# photon_proto_shield.net
KiCad netlist of a schematic drawn in EAGLE
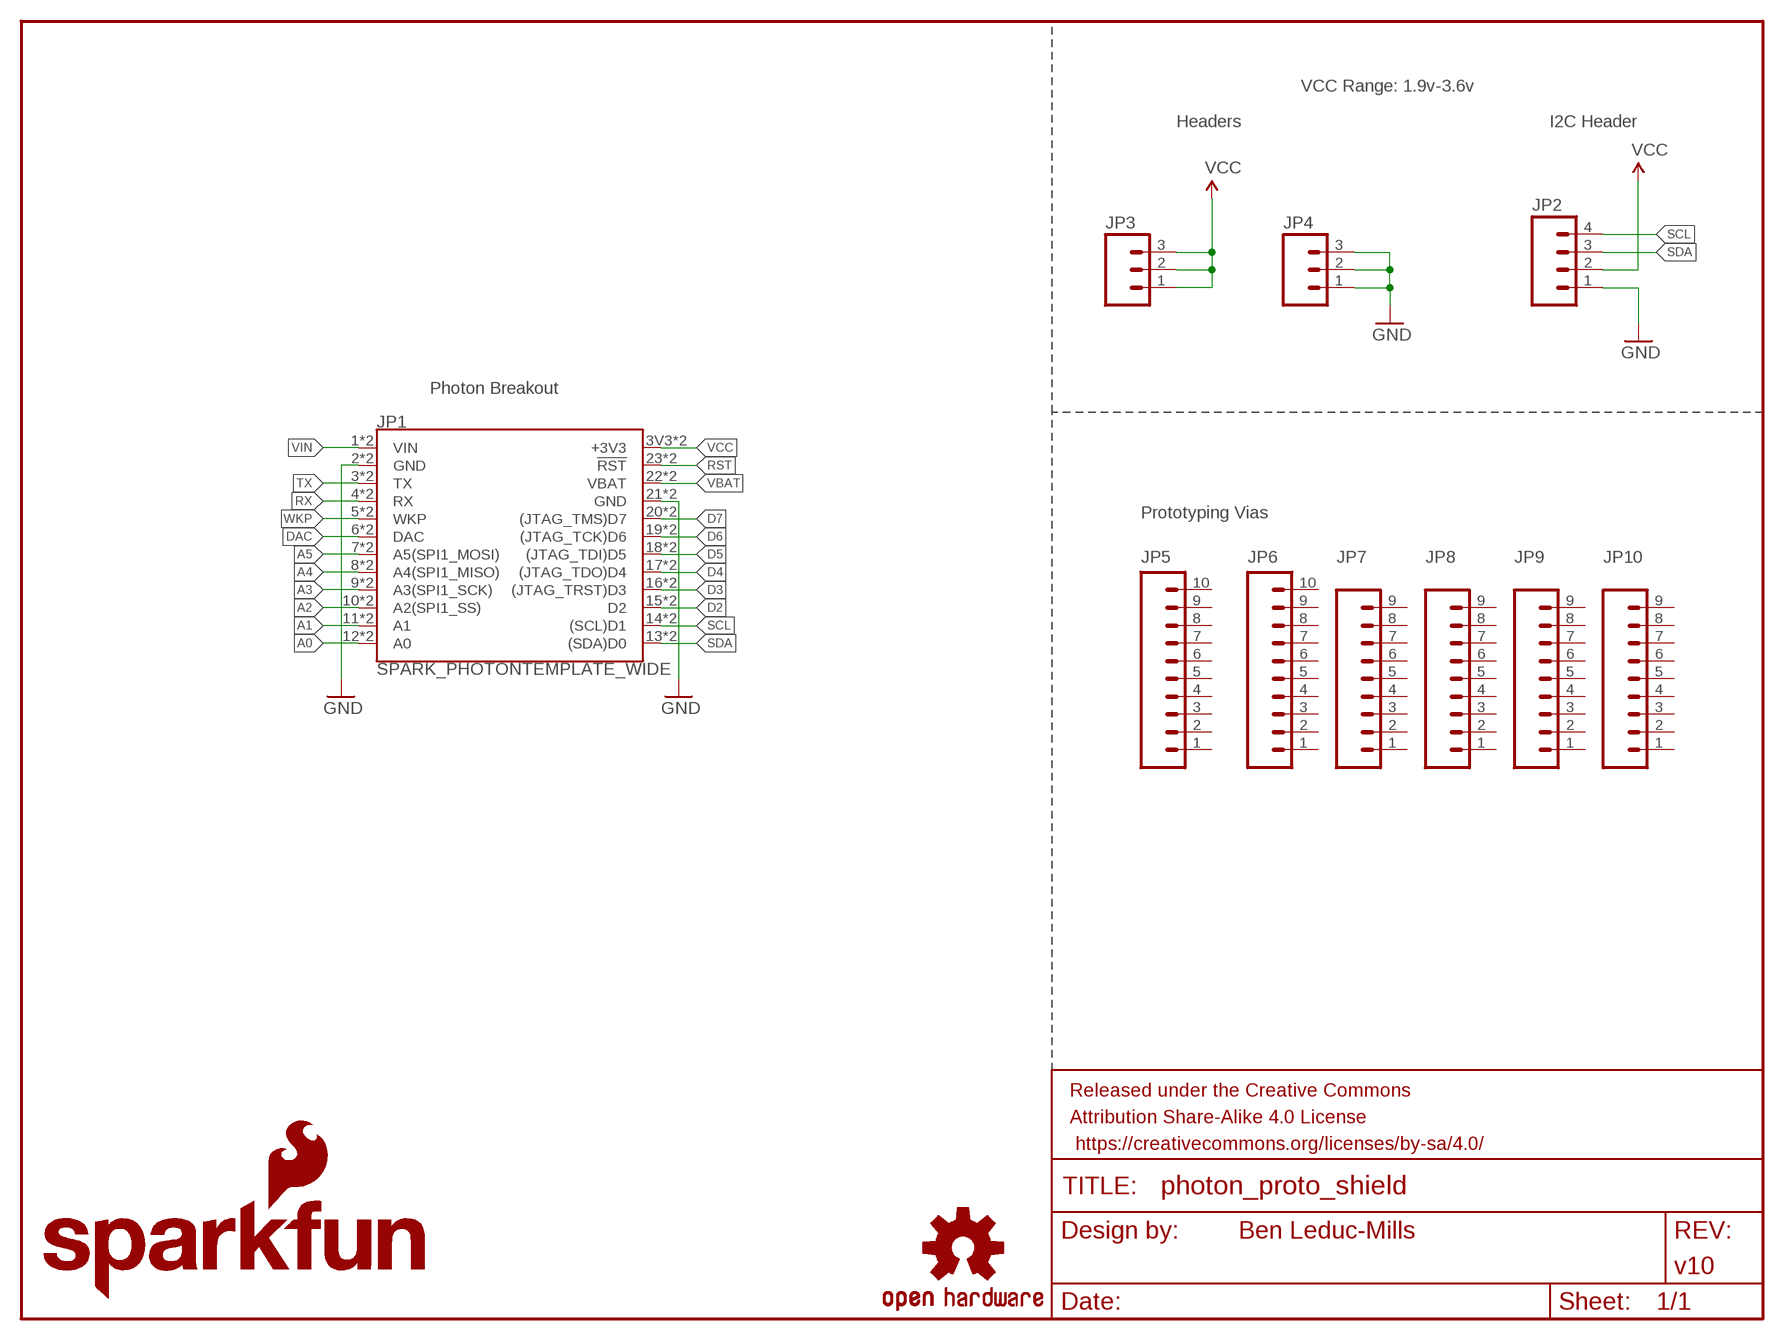
[diagram p0: schematic, sheet 1]

(export (version "E")
  (design (tool "Eeschema 10.0.6"))
  (components
    (comp (ref "FRAME1")
      (value "FRAME-LETTER")
      (footprint "eagle-import:CREATIVE_COMMONS")
      (fields (field (name "DESIGNER") "Ben Leduc-Mills") (field (name "VERSION") "v10"))
      (libsource (lib "eagle-import") (part "FRAME-LETTER"))
    )
    (comp (ref "JP1")
      (value "SPARK_PHOTONTEMPLATE_WIDE")
      (footprint "eagle-import:SPARK_PHOTON_TEMPLATE_WIDE")
      (libsource (lib "eagle-import") (part "SPARK_PHOTONTEMPLATE_WIDE"))
    )
    (comp (ref "JP2")
      (value "M04PTH")
      (footprint "eagle-import:1X04")
      (libsource (lib "eagle-import") (part "M04PTH"))
    )
    (comp (ref "JP3")
      (value "M03PTH")
      (footprint "eagle-import:1X03")
      (libsource (lib "eagle-import") (part "M03PTH"))
    )
    (comp (ref "JP4")
      (value "M03PTH")
      (footprint "eagle-import:1X03")
      (libsource (lib "eagle-import") (part "M03PTH"))
    )
    (comp (ref "JP5")
      (value "M10NO_SILK_PTH_FEMALE")
      (footprint "eagle-import:1X10_NO_SILK")
      (libsource (lib "eagle-import") (part "M10NO_SILK_PTH_FEMALE"))
    )
    (comp (ref "JP6")
      (value "M10NO_SILK_PTH_FEMALE")
      (footprint "eagle-import:1X10_NO_SILK")
      (libsource (lib "eagle-import") (part "M10NO_SILK_PTH_FEMALE"))
    )
    (comp (ref "JP7")
      (value "M09NO_SILK")
      (footprint "eagle-import:1X09_NO_SILK")
      (libsource (lib "eagle-import") (part "M09NO_SILK"))
    )
    (comp (ref "JP8")
      (value "M09NO_SILK")
      (footprint "eagle-import:1X09_NO_SILK")
      (libsource (lib "eagle-import") (part "M09NO_SILK"))
    )
    (comp (ref "JP9")
      (value "M09NO_SILK")
      (footprint "eagle-import:1X09_NO_SILK")
      (libsource (lib "eagle-import") (part "M09NO_SILK"))
    )
    (comp (ref "JP10")
      (value "M09NO_SILK")
      (footprint "eagle-import:1X09_NO_SILK")
      (libsource (lib "eagle-import") (part "M09NO_SILK"))
    )
    (comp (ref "LOGO1")
      (value "SFE_LOGO_NAME_FLAME.1_INCH")
      (footprint "eagle-import:SFE_LOGO_NAME_FLAME_.1")
      (libsource (lib "eagle-import") (part "SFE_LOGO_NAME_FLAME.1_INCH"))
    )
    (comp (ref "LOGO2")
      (value "OSHW-LOGOS")
      (footprint "eagle-import:OSHW-LOGO-S")
      (libsource (lib "eagle-import") (part "OSHW-LOGOS"))
    )
  )
  (nets
    (net (code "1") (name "A0") (class "Default")
      (node (ref "JP1") (pin "12") (pinfunction "A0_12") (pintype "bidirectional"))
      (node (ref "JP1") (pin "A0") (pinfunction "A0_A0") (pintype "bidirectional"))
    )
    (net (code "2") (name "A1") (class "Default")
      (node (ref "JP1") (pin "11") (pinfunction "A1_11") (pintype "bidirectional"))
      (node (ref "JP1") (pin "A1") (pinfunction "A1_A1") (pintype "bidirectional"))
    )
    (net (code "3") (name "A2") (class "Default")
      (node (ref "JP1") (pin "10") (pinfunction "A2(SPI1_SS)_10") (pintype "bidirectional"))
      (node (ref "JP1") (pin "A2") (pinfunction "A2(SPI1_SS)_A2") (pintype "bidirectional"))
    )
    (net (code "4") (name "A3") (class "Default")
      (node (ref "JP1") (pin "9") (pinfunction "A3(SPI1_SCK)_9") (pintype "bidirectional"))
      (node (ref "JP1") (pin "A3") (pinfunction "A3(SPI1_SCK)_A3") (pintype "bidirectional"))
    )
    (net (code "5") (name "A4") (class "Default")
      (node (ref "JP1") (pin "8") (pinfunction "A4(SPI1_MISO)_8") (pintype "bidirectional"))
      (node (ref "JP1") (pin "A4") (pinfunction "A4(SPI1_MISO)_A4") (pintype "bidirectional"))
    )
    (net (code "6") (name "A5") (class "Default")
      (node (ref "JP1") (pin "7") (pinfunction "A5(SPI1_MOSI)_7") (pintype "bidirectional"))
      (node (ref "JP1") (pin "A5") (pinfunction "A5(SPI1_MOSI)_A5") (pintype "bidirectional"))
    )
    (net (code "7") (name "D2") (class "Default")
      (node (ref "JP1") (pin "15") (pinfunction "D2_15") (pintype "bidirectional"))
      (node (ref "JP1") (pin "D2") (pinfunction "D2_D2") (pintype "bidirectional"))
    )
    (net (code "8") (name "D3") (class "Default")
      (node (ref "JP1") (pin "16") (pinfunction "(JTAG_TRST)D3_16") (pintype "bidirectional"))
      (node (ref "JP1") (pin "D3") (pinfunction "(JTAG_TRST)D3_D3") (pintype "bidirectional"))
    )
    (net (code "9") (name "D4") (class "Default")
      (node (ref "JP1") (pin "17") (pinfunction "(JTAG_TDO)D4_17") (pintype "bidirectional"))
      (node (ref "JP1") (pin "D4") (pinfunction "(JTAG_TDO)D4_D4") (pintype "bidirectional"))
    )
    (net (code "10") (name "D5") (class "Default")
      (node (ref "JP1") (pin "18") (pinfunction "(JTAG_TDI)D5_18") (pintype "bidirectional"))
      (node (ref "JP1") (pin "D5") (pinfunction "(JTAG_TDI)D5_D5") (pintype "bidirectional"))
    )
    (net (code "11") (name "D6") (class "Default")
      (node (ref "JP1") (pin "19") (pinfunction "(JTAG_TCK)D6_19") (pintype "bidirectional"))
      (node (ref "JP1") (pin "D6") (pinfunction "(JTAG_TCK)D6_D6") (pintype "bidirectional"))
    )
    (net (code "12") (name "D7") (class "Default")
      (node (ref "JP1") (pin "20") (pinfunction "(JTAG_TMS)D7_20") (pintype "bidirectional"))
      (node (ref "JP1") (pin "D7") (pinfunction "(JTAG_TMS)D7_D7") (pintype "bidirectional"))
    )
    (net (code "13") (name "DAC") (class "Default")
      (node (ref "JP1") (pin "6") (pinfunction "DAC_6") (pintype "bidirectional"))
      (node (ref "JP1") (pin "DAC") (pinfunction "DAC_DAC") (pintype "bidirectional"))
    )
    (net (code "14") (name "GND") (class "Default")
      (node (ref "JP1") (pin "2") (pinfunction "GND_2") (pintype "bidirectional"))
      (node (ref "JP1") (pin "21") (pinfunction "GND_21") (pintype "bidirectional"))
      (node (ref "JP1") (pin "GND@0") (pinfunction "GND_GND@0") (pintype "bidirectional"))
      (node (ref "JP1") (pin "GND@2") (pinfunction "GND_GND@2") (pintype "bidirectional"))
      (node (ref "JP2") (pin "1") (pinfunction "1_1") (pintype "passive"))
      (node (ref "JP4") (pin "1") (pinfunction "1_1") (pintype "passive"))
      (node (ref "JP4") (pin "2") (pinfunction "2_2") (pintype "passive"))
      (node (ref "JP4") (pin "3") (pinfunction "3_3") (pintype "passive"))
    )
    (net (code "15") (name "RST") (class "Default")
      (node (ref "JP1") (pin "23") (pinfunction "~{RST}_23") (pintype "bidirectional"))
      (node (ref "JP1") (pin "RST") (pinfunction "~{RST}_RST") (pintype "bidirectional"))
    )
    (net (code "16") (name "RX") (class "Default")
      (node (ref "JP1") (pin "4") (pinfunction "RX_4") (pintype "bidirectional"))
      (node (ref "JP1") (pin "RX") (pinfunction "RX_RX") (pintype "bidirectional"))
    )
    (net (code "17") (name "SCL") (class "Default")
      (node (ref "JP1") (pin "14") (pinfunction "(SCL)D1_14") (pintype "bidirectional"))
      (node (ref "JP1") (pin "D1") (pinfunction "(SCL)D1_D1") (pintype "bidirectional"))
      (node (ref "JP2") (pin "4") (pinfunction "4_4") (pintype "passive"))
    )
    (net (code "18") (name "SDA") (class "Default")
      (node (ref "JP1") (pin "13") (pinfunction "(SDA)D0_13") (pintype "bidirectional"))
      (node (ref "JP1") (pin "D0") (pinfunction "(SDA)D0_D0") (pintype "bidirectional"))
      (node (ref "JP2") (pin "3") (pinfunction "3_3") (pintype "passive"))
    )
    (net (code "19") (name "TX") (class "Default")
      (node (ref "JP1") (pin "3") (pinfunction "TX_3") (pintype "bidirectional"))
      (node (ref "JP1") (pin "TX") (pinfunction "TX_TX") (pintype "bidirectional"))
    )
    (net (code "20") (name "VBAT") (class "Default")
      (node (ref "JP1") (pin "22") (pinfunction "VBAT_22") (pintype "bidirectional"))
      (node (ref "JP1") (pin "VBAT") (pinfunction "VBAT_VBAT") (pintype "bidirectional"))
    )
    (net (code "21") (name "VCC") (class "Default")
      (node (ref "JP1") (pin "24") (pinfunction "+3V3_24") (pintype "bidirectional"))
      (node (ref "JP1") (pin "3V3") (pinfunction "+3V3_3V3") (pintype "bidirectional"))
      (node (ref "JP2") (pin "2") (pinfunction "2_2") (pintype "passive"))
      (node (ref "JP3") (pin "1") (pinfunction "1_1") (pintype "passive"))
      (node (ref "JP3") (pin "2") (pinfunction "2_2") (pintype "passive"))
      (node (ref "JP3") (pin "3") (pinfunction "3_3") (pintype "passive"))
    )
    (net (code "22") (name "VIN") (class "Default")
      (node (ref "JP1") (pin "1") (pinfunction "VIN_1") (pintype "bidirectional"))
      (node (ref "JP1") (pin "VIN") (pinfunction "VIN_VIN") (pintype "bidirectional"))
    )
    (net (code "23") (name "WKP") (class "Default")
      (node (ref "JP1") (pin "5") (pinfunction "WKP_5") (pintype "bidirectional"))
      (node (ref "JP1") (pin "WKP") (pinfunction "WKP_WKP") (pintype "bidirectional"))
    )
    (net (code "24") (name "unconnected-(JP5-Pad1)") (class "Default")
      (node (ref "JP5") (pin "1") (pinfunction "1_1") (pintype "passive"))
    )
    (net (code "25") (name "unconnected-(JP5-Pad2)") (class "Default")
      (node (ref "JP5") (pin "2") (pinfunction "2_2") (pintype "passive"))
    )
    (net (code "26") (name "unconnected-(JP5-Pad3)") (class "Default")
      (node (ref "JP5") (pin "3") (pinfunction "3_3") (pintype "passive"))
    )
    (net (code "27") (name "unconnected-(JP5-Pad4)") (class "Default")
      (node (ref "JP5") (pin "4") (pinfunction "4_4") (pintype "passive"))
    )
    (net (code "28") (name "unconnected-(JP5-Pad5)") (class "Default")
      (node (ref "JP5") (pin "5") (pinfunction "5_5") (pintype "passive"))
    )
    (net (code "29") (name "unconnected-(JP5-Pad6)") (class "Default")
      (node (ref "JP5") (pin "6") (pinfunction "6_6") (pintype "passive"))
    )
    (net (code "30") (name "unconnected-(JP5-Pad7)") (class "Default")
      (node (ref "JP5") (pin "7") (pinfunction "7_7") (pintype "passive"))
    )
    (net (code "31") (name "unconnected-(JP5-Pad8)") (class "Default")
      (node (ref "JP5") (pin "8") (pinfunction "8_8") (pintype "passive"))
    )
    (net (code "32") (name "unconnected-(JP5-Pad9)") (class "Default")
      (node (ref "JP5") (pin "9") (pinfunction "9_9") (pintype "passive"))
    )
    (net (code "33") (name "unconnected-(JP5-Pad10)") (class "Default")
      (node (ref "JP5") (pin "10") (pinfunction "10_10") (pintype "passive"))
    )
    (net (code "34") (name "unconnected-(JP6-Pad1)") (class "Default")
      (node (ref "JP6") (pin "1") (pinfunction "1_1") (pintype "passive"))
    )
    (net (code "35") (name "unconnected-(JP6-Pad2)") (class "Default")
      (node (ref "JP6") (pin "2") (pinfunction "2_2") (pintype "passive"))
    )
    (net (code "36") (name "unconnected-(JP6-Pad3)") (class "Default")
      (node (ref "JP6") (pin "3") (pinfunction "3_3") (pintype "passive"))
    )
    (net (code "37") (name "unconnected-(JP6-Pad4)") (class "Default")
      (node (ref "JP6") (pin "4") (pinfunction "4_4") (pintype "passive"))
    )
    (net (code "38") (name "unconnected-(JP6-Pad5)") (class "Default")
      (node (ref "JP6") (pin "5") (pinfunction "5_5") (pintype "passive"))
    )
    (net (code "39") (name "unconnected-(JP6-Pad6)") (class "Default")
      (node (ref "JP6") (pin "6") (pinfunction "6_6") (pintype "passive"))
    )
    (net (code "40") (name "unconnected-(JP6-Pad7)") (class "Default")
      (node (ref "JP6") (pin "7") (pinfunction "7_7") (pintype "passive"))
    )
    (net (code "41") (name "unconnected-(JP6-Pad8)") (class "Default")
      (node (ref "JP6") (pin "8") (pinfunction "8_8") (pintype "passive"))
    )
    (net (code "42") (name "unconnected-(JP6-Pad9)") (class "Default")
      (node (ref "JP6") (pin "9") (pinfunction "9_9") (pintype "passive"))
    )
    (net (code "43") (name "unconnected-(JP6-Pad10)") (class "Default")
      (node (ref "JP6") (pin "10") (pinfunction "10_10") (pintype "passive"))
    )
    (net (code "44") (name "unconnected-(JP7-Pad1)") (class "Default")
      (node (ref "JP7") (pin "1") (pinfunction "1_1") (pintype "passive"))
    )
    (net (code "45") (name "unconnected-(JP7-Pad2)") (class "Default")
      (node (ref "JP7") (pin "2") (pinfunction "2_2") (pintype "passive"))
    )
    (net (code "46") (name "unconnected-(JP7-Pad3)") (class "Default")
      (node (ref "JP7") (pin "3") (pinfunction "3_3") (pintype "passive"))
    )
    (net (code "47") (name "unconnected-(JP7-Pad4)") (class "Default")
      (node (ref "JP7") (pin "4") (pinfunction "4_4") (pintype "passive"))
    )
    (net (code "48") (name "unconnected-(JP7-Pad5)") (class "Default")
      (node (ref "JP7") (pin "5") (pinfunction "5_5") (pintype "passive"))
    )
    (net (code "49") (name "unconnected-(JP7-Pad6)") (class "Default")
      (node (ref "JP7") (pin "6") (pinfunction "6_6") (pintype "passive"))
    )
    (net (code "50") (name "unconnected-(JP7-Pad7)") (class "Default")
      (node (ref "JP7") (pin "7") (pinfunction "7_7") (pintype "passive"))
    )
    (net (code "51") (name "unconnected-(JP7-Pad8)") (class "Default")
      (node (ref "JP7") (pin "8") (pinfunction "8_8") (pintype "passive"))
    )
    (net (code "52") (name "unconnected-(JP7-Pad9)") (class "Default")
      (node (ref "JP7") (pin "9") (pinfunction "9_9") (pintype "passive"))
    )
    (net (code "53") (name "unconnected-(JP8-Pad1)") (class "Default")
      (node (ref "JP8") (pin "1") (pinfunction "1_1") (pintype "passive"))
    )
    (net (code "54") (name "unconnected-(JP8-Pad2)") (class "Default")
      (node (ref "JP8") (pin "2") (pinfunction "2_2") (pintype "passive"))
    )
    (net (code "55") (name "unconnected-(JP8-Pad3)") (class "Default")
      (node (ref "JP8") (pin "3") (pinfunction "3_3") (pintype "passive"))
    )
    (net (code "56") (name "unconnected-(JP8-Pad4)") (class "Default")
      (node (ref "JP8") (pin "4") (pinfunction "4_4") (pintype "passive"))
    )
    (net (code "57") (name "unconnected-(JP8-Pad5)") (class "Default")
      (node (ref "JP8") (pin "5") (pinfunction "5_5") (pintype "passive"))
    )
    (net (code "58") (name "unconnected-(JP8-Pad6)") (class "Default")
      (node (ref "JP8") (pin "6") (pinfunction "6_6") (pintype "passive"))
    )
    (net (code "59") (name "unconnected-(JP8-Pad7)") (class "Default")
      (node (ref "JP8") (pin "7") (pinfunction "7_7") (pintype "passive"))
    )
    (net (code "60") (name "unconnected-(JP8-Pad8)") (class "Default")
      (node (ref "JP8") (pin "8") (pinfunction "8_8") (pintype "passive"))
    )
    (net (code "61") (name "unconnected-(JP8-Pad9)") (class "Default")
      (node (ref "JP8") (pin "9") (pinfunction "9_9") (pintype "passive"))
    )
    (net (code "62") (name "unconnected-(JP9-Pad1)") (class "Default")
      (node (ref "JP9") (pin "1") (pinfunction "1_1") (pintype "passive"))
    )
    (net (code "63") (name "unconnected-(JP9-Pad2)") (class "Default")
      (node (ref "JP9") (pin "2") (pinfunction "2_2") (pintype "passive"))
    )
    (net (code "64") (name "unconnected-(JP9-Pad3)") (class "Default")
      (node (ref "JP9") (pin "3") (pinfunction "3_3") (pintype "passive"))
    )
    (net (code "65") (name "unconnected-(JP9-Pad4)") (class "Default")
      (node (ref "JP9") (pin "4") (pinfunction "4_4") (pintype "passive"))
    )
    (net (code "66") (name "unconnected-(JP9-Pad5)") (class "Default")
      (node (ref "JP9") (pin "5") (pinfunction "5_5") (pintype "passive"))
    )
    (net (code "67") (name "unconnected-(JP9-Pad6)") (class "Default")
      (node (ref "JP9") (pin "6") (pinfunction "6_6") (pintype "passive"))
    )
    (net (code "68") (name "unconnected-(JP9-Pad7)") (class "Default")
      (node (ref "JP9") (pin "7") (pinfunction "7_7") (pintype "passive"))
    )
    (net (code "69") (name "unconnected-(JP9-Pad8)") (class "Default")
      (node (ref "JP9") (pin "8") (pinfunction "8_8") (pintype "passive"))
    )
    (net (code "70") (name "unconnected-(JP9-Pad9)") (class "Default")
      (node (ref "JP9") (pin "9") (pinfunction "9_9") (pintype "passive"))
    )
    (net (code "71") (name "unconnected-(JP10-Pad1)") (class "Default")
      (node (ref "JP10") (pin "1") (pinfunction "1_1") (pintype "passive"))
    )
    (net (code "72") (name "unconnected-(JP10-Pad2)") (class "Default")
      (node (ref "JP10") (pin "2") (pinfunction "2_2") (pintype "passive"))
    )
    (net (code "73") (name "unconnected-(JP10-Pad3)") (class "Default")
      (node (ref "JP10") (pin "3") (pinfunction "3_3") (pintype "passive"))
    )
    (net (code "74") (name "unconnected-(JP10-Pad4)") (class "Default")
      (node (ref "JP10") (pin "4") (pinfunction "4_4") (pintype "passive"))
    )
    (net (code "75") (name "unconnected-(JP10-Pad5)") (class "Default")
      (node (ref "JP10") (pin "5") (pinfunction "5_5") (pintype "passive"))
    )
    (net (code "76") (name "unconnected-(JP10-Pad6)") (class "Default")
      (node (ref "JP10") (pin "6") (pinfunction "6_6") (pintype "passive"))
    )
    (net (code "77") (name "unconnected-(JP10-Pad7)") (class "Default")
      (node (ref "JP10") (pin "7") (pinfunction "7_7") (pintype "passive"))
    )
    (net (code "78") (name "unconnected-(JP10-Pad8)") (class "Default")
      (node (ref "JP10") (pin "8") (pinfunction "8_8") (pintype "passive"))
    )
    (net (code "79") (name "unconnected-(JP10-Pad9)") (class "Default")
      (node (ref "JP10") (pin "9") (pinfunction "9_9") (pintype "passive"))
    )
  )
)
